# Alarm_and_Security_System.net
KiCad netlist of a schematic drawn in EAGLE
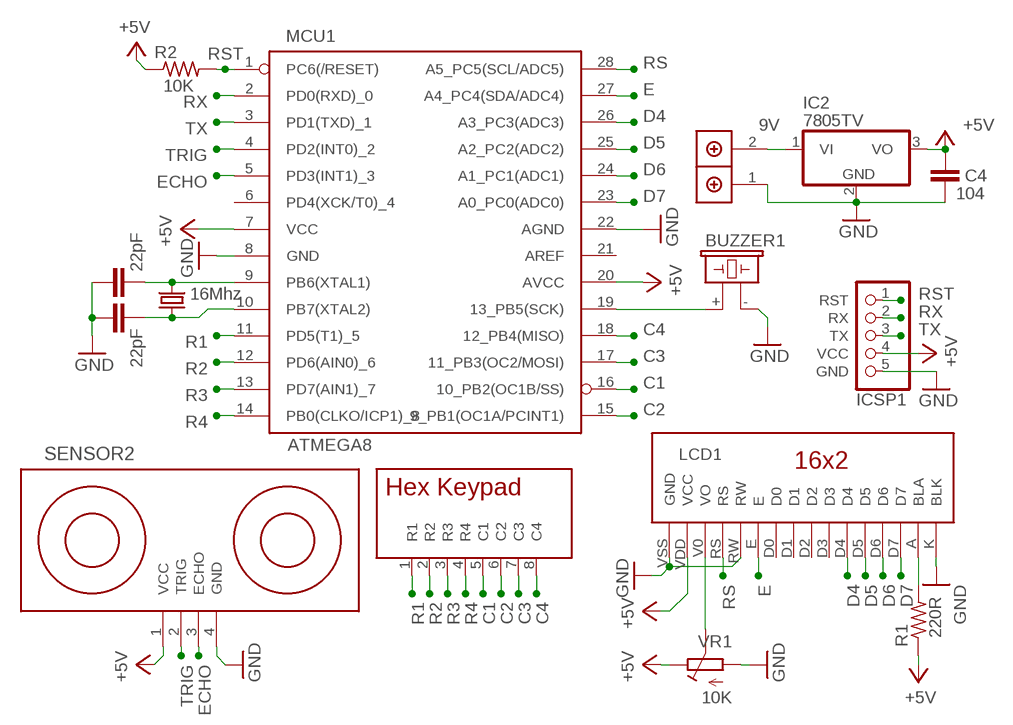
[diagram p0: schematic, sheet 1]

(export (version "E")
  (design (tool "Eeschema 10.0.6"))
  (components
    (comp (ref "BUZZER1")
      (value "F/CM12P")
      (footprint "eagle-import:F_CM12P")
      (libsource (lib "eagle-import") (part "F/CM12P"))
    )
    (comp (ref "C1")
      (value "22pF")
      (footprint "eagle-import:22PF")
      (libsource (lib "eagle-import") (part "22PF"))
    )
    (comp (ref "C2")
      (value "22pF")
      (footprint "eagle-import:22PF")
      (libsource (lib "eagle-import") (part "22PF"))
    )
    (comp (ref "C4")
      (value "104")
      (footprint "eagle-import:104")
      (libsource (lib "eagle-import") (part "104"))
    )
    (comp (ref "IC2")
      (value "7805TV")
      (footprint "eagle-import:TO220V")
      (libsource (lib "eagle-import") (part "78TV05"))
    )
    (comp (ref "ICSP1")
      (value "ICSP_ATMEGA328")
      (footprint "eagle-import:ICSP_ATMEGA")
      (libsource (lib "eagle-import") (part "ICSP_ATMEGA328"))
    )
    (comp (ref "KEYPAD1")
      (value "HEX_KEYPAD")
      (footprint "eagle-import:HEX_KEYPAD")
      (libsource (lib "eagle-import") (part "HEX_KEYPAD"))
    )
    (comp (ref "LCD1")
      (value "16X2_LCD")
      (footprint "eagle-import:16X2_LCD")
      (libsource (lib "eagle-import") (part "16X2_LCD"))
    )
    (comp (ref "MCU1")
      (value "ATMEGA8")
      (footprint "eagle-import:ATMEGA328_P")
      (libsource (lib "eagle-import") (part "ATMEGA328_P"))
    )
    (comp (ref "Q1")
      (value "16Mhz")
      (footprint "eagle-import:CRYSTAL")
      (libsource (lib "eagle-import") (part "CRYSTAL"))
    )
    (comp (ref "R1")
      (value "220R")
      (footprint "eagle-import:THR_R_204_7")
      (libsource (lib "eagle-import") (part "RES204/7"))
    )
    (comp (ref "R2")
      (value "10K")
      (footprint "eagle-import:THR_R_204_7")
      (libsource (lib "eagle-import") (part "RES204/7"))
    )
    (comp (ref "SENSOR2")
      (value "ULTRASONIC-HC-SR04SONAR")
      (footprint "eagle-import:1X04")
      (libsource (lib "eagle-import") (part "ULTRASONIC-HC-SR04SONAR"))
    )
    (comp (ref "TB2") (value "2P") (footprint "eagle-import:2P") (libsource (lib "eagle-import") (part "2P")))
    (comp (ref "VR1")
      (value "10K")
      (footprint "eagle-import:BLUE_VR")
      (libsource (lib "eagle-import") (part "BLUE_VR"))
    )
  )
  (nets
    (net (code "1") (name "+5V") (class "Default")
      (node (ref "C4") (pin "1") (pinfunction "1_1") (pintype "passive"))
      (node (ref "IC2") (pin "3") (pinfunction "VO_3") (pintype "passive"))
      (node (ref "ICSP1") (pin "4") (pinfunction "VCC_4") (pintype "bidirectional"))
      (node (ref "LCD1") (pin "VDD") (pinfunction "VCC_VDD") (pintype "bidirectional"))
      (node (ref "MCU1") (pin "20") (pinfunction "AVCC_20") (pintype "power_in"))
      (node (ref "MCU1") (pin "7") (pinfunction "VCC_7") (pintype "power_in"))
      (node (ref "R1") (pin "1") (pinfunction "1_1") (pintype "passive"))
      (node (ref "R2") (pin "1") (pinfunction "1_1") (pintype "passive"))
      (node (ref "SENSOR2") (pin "1") (pinfunction "VCC_1") (pintype "power_in"))
      (node (ref "VR1") (pin "1") (pinfunction "1_1") (pintype "bidirectional"))
    )
    (net (code "2") (name "/9V") (class "Default")
      (node (ref "IC2") (pin "1") (pinfunction "VI_1") (pintype "input"))
      (node (ref "TB2") (pin "2") (pinfunction "CONN2_2") (pintype "bidirectional"))
    )
    (net (code "3") (name "/C1") (class "Default")
      (node (ref "KEYPAD1") (pin "5") (pinfunction "C1_5") (pintype "bidirectional"))
      (node (ref "MCU1") (pin "16") (pinfunction "10_PB2(OC1B/SS)_16") (pintype "bidirectional"))
    )
    (net (code "4") (name "/C2") (class "Default")
      (node (ref "KEYPAD1") (pin "6") (pinfunction "C2_6") (pintype "bidirectional"))
      (node (ref "MCU1") (pin "15") (pinfunction "9_PB1(OC1A/PCINT1)_15") (pintype "bidirectional"))
    )
    (net (code "5") (name "/C3") (class "Default")
      (node (ref "KEYPAD1") (pin "7") (pinfunction "C3_7") (pintype "bidirectional"))
      (node (ref "MCU1") (pin "17") (pinfunction "11_PB3(OC2/MOSI)_17") (pintype "bidirectional"))
    )
    (net (code "6") (name "/C4") (class "Default")
      (node (ref "KEYPAD1") (pin "8") (pinfunction "C4_8") (pintype "bidirectional"))
      (node (ref "MCU1") (pin "18") (pinfunction "12_PB4(MISO)_18") (pintype "bidirectional"))
    )
    (net (code "7") (name "/D4") (class "Default")
      (node (ref "LCD1") (pin "D4") (pinfunction "D4_D4") (pintype "bidirectional"))
      (node (ref "MCU1") (pin "26") (pinfunction "A3_PC3(ADC3)_26") (pintype "bidirectional"))
    )
    (net (code "8") (name "/D5") (class "Default")
      (node (ref "LCD1") (pin "D5") (pinfunction "D5_D5") (pintype "bidirectional"))
      (node (ref "MCU1") (pin "25") (pinfunction "A2_PC2(ADC2)_25") (pintype "bidirectional"))
    )
    (net (code "9") (name "/D6") (class "Default")
      (node (ref "LCD1") (pin "D6") (pinfunction "D6_D6") (pintype "bidirectional"))
      (node (ref "MCU1") (pin "24") (pinfunction "A1_PC1(ADC1)_24") (pintype "bidirectional"))
    )
    (net (code "10") (name "/D7") (class "Default")
      (node (ref "LCD1") (pin "D7") (pinfunction "D7_D7") (pintype "bidirectional"))
      (node (ref "MCU1") (pin "23") (pinfunction "A0_PC0(ADC0)_23") (pintype "bidirectional"))
    )
    (net (code "11") (name "/E") (class "Default")
      (node (ref "LCD1") (pin "E") (pinfunction "E_E") (pintype "bidirectional"))
      (node (ref "MCU1") (pin "27") (pinfunction "A4_PC4(SDA/ADC4)_27") (pintype "bidirectional"))
    )
    (net (code "12") (name "/ECHO") (class "Default")
      (node (ref "MCU1") (pin "5") (pinfunction "PD3(INT1)_3_5") (pintype "bidirectional"))
      (node (ref "SENSOR2") (pin "3") (pinfunction "ECHO_3") (pintype "output"))
    )
    (net (code "13") (name "/R1") (class "Default")
      (node (ref "KEYPAD1") (pin "1") (pinfunction "R1_1") (pintype "bidirectional"))
      (node (ref "MCU1") (pin "11") (pinfunction "PD5(T1)_5_11") (pintype "bidirectional"))
    )
    (net (code "14") (name "/R2") (class "Default")
      (node (ref "KEYPAD1") (pin "2") (pinfunction "R2_2") (pintype "bidirectional"))
      (node (ref "MCU1") (pin "12") (pinfunction "PD6(AIN0)_6_12") (pintype "bidirectional"))
    )
    (net (code "15") (name "/R3") (class "Default")
      (node (ref "KEYPAD1") (pin "3") (pinfunction "R3_3") (pintype "bidirectional"))
      (node (ref "MCU1") (pin "13") (pinfunction "PD7(AIN1)_7_13") (pintype "bidirectional"))
    )
    (net (code "16") (name "/R4") (class "Default")
      (node (ref "KEYPAD1") (pin "4") (pinfunction "R4_4") (pintype "bidirectional"))
      (node (ref "MCU1") (pin "14") (pinfunction "PB0(CLKO/ICP1)_8_14") (pintype "bidirectional"))
    )
    (net (code "17") (name "/RS") (class "Default")
      (node (ref "LCD1") (pin "RS") (pinfunction "RS_RS") (pintype "bidirectional"))
      (node (ref "MCU1") (pin "28") (pinfunction "A5_PC5(SCL/ADC5)_28") (pintype "bidirectional"))
    )
    (net (code "18") (name "/RST") (class "Default")
      (node (ref "ICSP1") (pin "1") (pinfunction "RST_1") (pintype "bidirectional"))
      (node (ref "MCU1") (pin "1") (pinfunction "PC6(/RESET)_1") (pintype "bidirectional"))
      (node (ref "R2") (pin "2") (pinfunction "2_2") (pintype "passive"))
    )
    (net (code "19") (name "/RX") (class "Default")
      (node (ref "ICSP1") (pin "2") (pinfunction "RX_2") (pintype "bidirectional"))
      (node (ref "MCU1") (pin "2") (pinfunction "PD0(RXD)_0_2") (pintype "bidirectional"))
    )
    (net (code "20") (name "/TRIG") (class "Default")
      (node (ref "MCU1") (pin "4") (pinfunction "PD2(INT0)_2_4") (pintype "bidirectional"))
      (node (ref "SENSOR2") (pin "2") (pinfunction "TRIG_2") (pintype "input"))
    )
    (net (code "21") (name "/TX") (class "Default")
      (node (ref "ICSP1") (pin "3") (pinfunction "TX_3") (pintype "bidirectional"))
      (node (ref "MCU1") (pin "3") (pinfunction "PD1(TXD)_1_3") (pintype "bidirectional"))
    )
    (net (code "22") (name "GND") (class "Default")
      (node (ref "BUZZER1") (pin "-") (pinfunction "2_-") (pintype "passive"))
      (node (ref "C1") (pin "1") (pinfunction "1_1") (pintype "passive"))
      (node (ref "C2") (pin "2") (pinfunction "2_2") (pintype "passive"))
      (node (ref "C4") (pin "2") (pinfunction "2_2") (pintype "passive"))
      (node (ref "IC2") (pin "2") (pinfunction "GND_2") (pintype "passive"))
      (node (ref "ICSP1") (pin "5") (pinfunction "GND_5") (pintype "bidirectional"))
      (node (ref "LCD1") (pin "K") (pinfunction "BLK_K") (pintype "bidirectional"))
      (node (ref "LCD1") (pin "RW") (pinfunction "RW_RW") (pintype "bidirectional"))
      (node (ref "LCD1") (pin "VSS") (pinfunction "GND_VSS") (pintype "bidirectional"))
      (node (ref "MCU1") (pin "22") (pinfunction "AGND_22") (pintype "power_in"))
      (node (ref "MCU1") (pin "8") (pinfunction "GND_8") (pintype "power_in"))
      (node (ref "SENSOR2") (pin "4") (pinfunction "GND_4") (pintype "power_in"))
      (node (ref "TB2") (pin "1") (pinfunction "CONN1_1") (pintype "bidirectional"))
      (node (ref "VR1") (pin "3") (pinfunction "3_3") (pintype "bidirectional"))
    )
    (net (code "23") (name "Net-(BUZZER1-1)") (class "Default")
      (node (ref "BUZZER1") (pin "+") (pinfunction "1_+") (pintype "passive"))
      (node (ref "MCU1") (pin "19") (pinfunction "13_PB5(SCK)_19") (pintype "bidirectional"))
    )
    (net (code "24") (name "Net-(LCD1-BLA)") (class "Default")
      (node (ref "LCD1") (pin "A") (pinfunction "BLA_A") (pintype "bidirectional"))
      (node (ref "R1") (pin "2") (pinfunction "2_2") (pintype "passive"))
    )
    (net (code "25") (name "Net-(LCD1-VO)") (class "Default")
      (node (ref "LCD1") (pin "V0") (pinfunction "VO_V0") (pintype "bidirectional"))
      (node (ref "VR1") (pin "2") (pinfunction "2_2") (pintype "bidirectional"))
    )
    (net (code "26") (name "Net-(MCU1-PB6(XTAL1))") (class "Default")
      (node (ref "C1") (pin "2") (pinfunction "2_2") (pintype "passive"))
      (node (ref "MCU1") (pin "9") (pinfunction "PB6(XTAL1)_9") (pintype "bidirectional"))
      (node (ref "Q1") (pin "2") (pinfunction "2_2") (pintype "passive"))
    )
    (net (code "27") (name "Net-(MCU1-PB7(XTAL2))") (class "Default")
      (node (ref "C2") (pin "1") (pinfunction "1_1") (pintype "passive"))
      (node (ref "MCU1") (pin "10") (pinfunction "PB7(XTAL2)_10") (pintype "bidirectional"))
      (node (ref "Q1") (pin "1") (pinfunction "1_1") (pintype "passive"))
    )
    (net (code "28") (name "unconnected-(LCD1-PadD0)") (class "Default")
      (node (ref "LCD1") (pin "D0") (pinfunction "D0_D0") (pintype "bidirectional"))
    )
    (net (code "29") (name "unconnected-(LCD1-PadD1)") (class "Default")
      (node (ref "LCD1") (pin "D1") (pinfunction "D1_D1") (pintype "bidirectional"))
    )
    (net (code "30") (name "unconnected-(LCD1-PadD2)") (class "Default")
      (node (ref "LCD1") (pin "D2") (pinfunction "D2_D2") (pintype "bidirectional"))
    )
    (net (code "31") (name "unconnected-(LCD1-PadD3)") (class "Default")
      (node (ref "LCD1") (pin "D3") (pinfunction "D3_D3") (pintype "bidirectional"))
    )
    (net (code "32") (name "unconnected-(MCU1-AREF-Pad21)") (class "Default")
      (node (ref "MCU1") (pin "21") (pinfunction "AREF_21") (pintype "passive"))
    )
    (net (code "33") (name "unconnected-(MCU1-PD4(XCK{slash}T0)_4-Pad6)") (class "Default")
      (node (ref "MCU1") (pin "6") (pinfunction "PD4(XCK/T0)_4_6") (pintype "bidirectional"))
    )
  )
)
